# 04_Debugging.net
KiCad netlist of a schematic drawn in Altium Designer
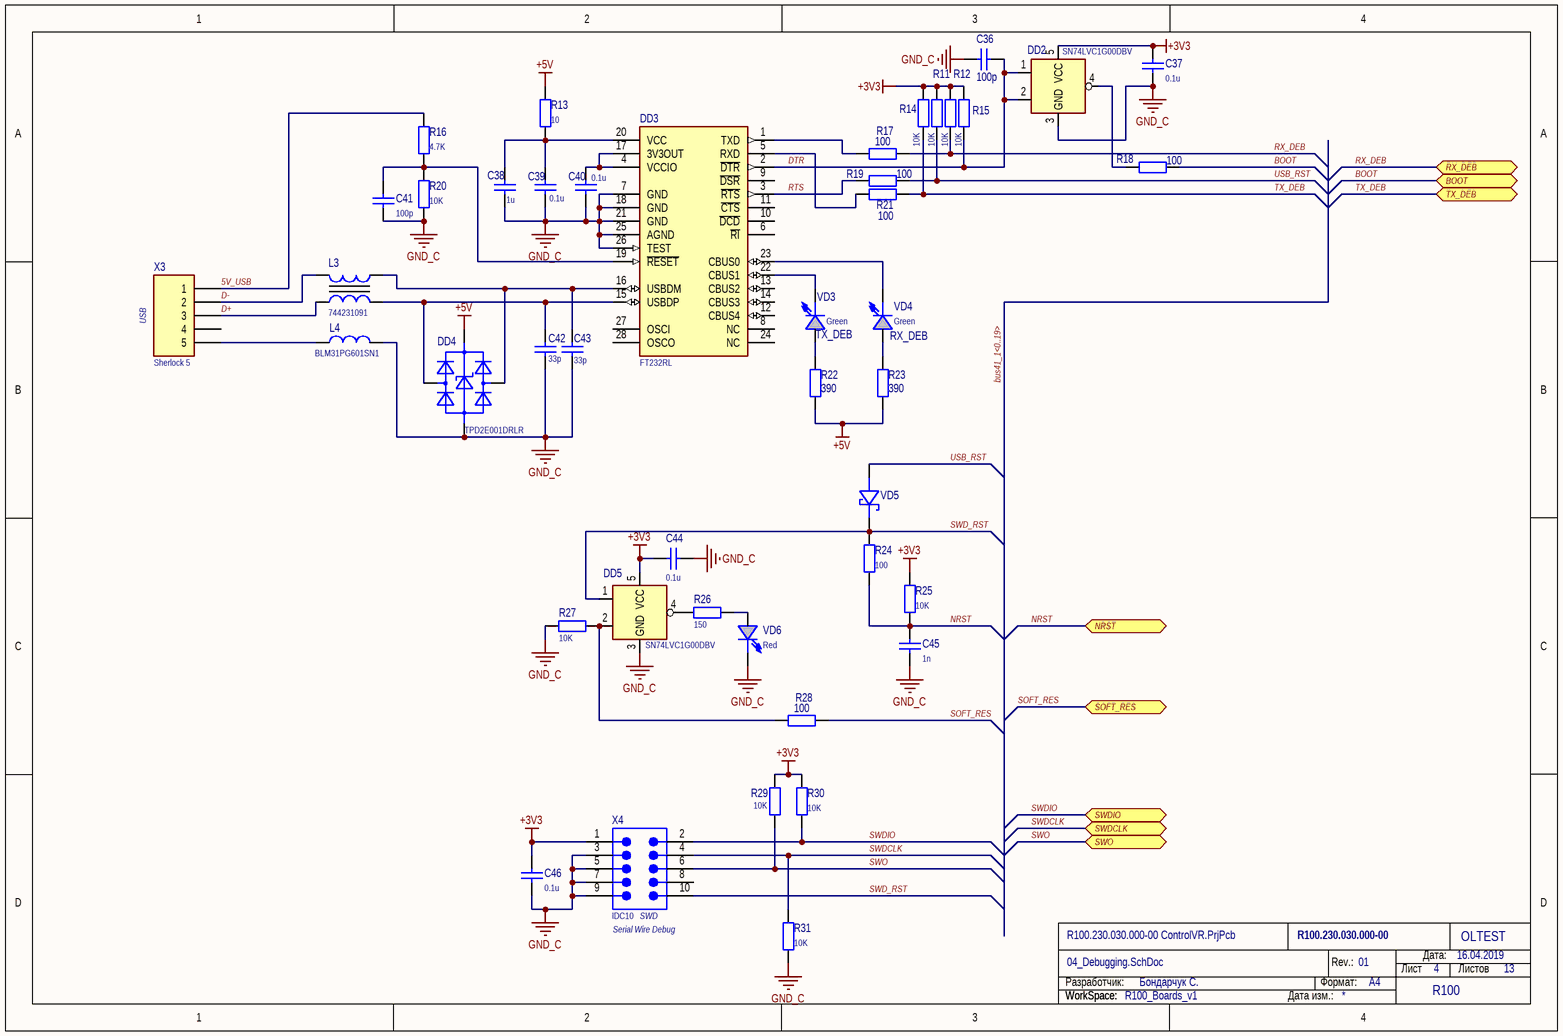
[diagram p0: 04_Debugging.SchDoc]

(export (version "E")
  (design (tool "Eeschema 10.0.6"))
  (components
    (comp (ref "C36")
      (value "100p")
      (footprint "mainLib:SMD_C_0603")
      (description "SMD C 0603 MURATA 100V 5% NP0")
      (fields (field (name "PARTNUMBER") "GRM1885C2A101JA01") (field (name "MANUFACTURER") "MURATA"))
      (libsource (lib "mainRCLib") (part "C0603 100p 100V 5%"))
    )
    (comp (ref "C37")
      (value "0.1u")
      (footprint "mainLib:SMD_C_0603")
      (description "SMD C 0603 MURATA 50V 10% X7R")
      (fields (field (name "PARTNUMBER") "GRM188R71H104K") (field (name "MANUFACTURER") "MURATA"))
      (libsource (lib "mainRCLib") (part "C0603 0.1u 50V 10%"))
    )
    (comp (ref "C38")
      (value "1u")
      (footprint "mainLib:SMD_C_0603")
      (description "SMD C 0603 MURATA 25V 10% X7R")
      (fields (field (name "PARTNUMBER") "GRM188R71E105KA12") (field (name "MANUFACTURER") "MURATA"))
      (libsource (lib "mainRCLib") (part "C0603 1uF 25V 10%"))
    )
    (comp (ref "C39")
      (value "0.1u")
      (footprint "mainLib:SMD_C_0603")
      (description "SMD C 0603 MURATA 50V 10% X7R")
      (fields (field (name "PARTNUMBER") "GRM188R71H104K") (field (name "MANUFACTURER") "MURATA"))
      (libsource (lib "mainRCLib") (part "C0603 0.1u 50V 10%"))
    )
    (comp (ref "C40")
      (value "0.1u")
      (footprint "mainLib:SMD_C_0603")
      (description "SMD C 0603 MURATA 50V 10% X7R")
      (fields (field (name "PARTNUMBER") "GRM188R71H104K") (field (name "MANUFACTURER") "MURATA"))
      (libsource (lib "mainRCLib") (part "C0603 0.1u 50V 10%"))
    )
    (comp (ref "C41")
      (value "100p")
      (footprint "mainLib:SMD_C_0603")
      (description "SMD C 0603 MURATA 100V 5% NP0")
      (fields (field (name "PARTNUMBER") "GRM1885C2A101JA01") (field (name "MANUFACTURER") "MURATA"))
      (libsource (lib "mainRCLib") (part "C0603 100p 100V 5%"))
    )
    (comp (ref "C42")
      (value "33p")
      (footprint "mainLib:SMD_C_0603")
      (description "SMD C 0603 MURATA 50V 5% NP0")
      (fields (field (name "PARTNUMBER") "GRM1885C1H330JA01") (field (name "MANUFACTURER") "MURATA"))
      (libsource (lib "mainRCLib") (part "C0603 33p 50V 5%"))
    )
    (comp (ref "C43")
      (value "33p")
      (footprint "mainLib:SMD_C_0603")
      (description "SMD C 0603 MURATA 50V 5% NP0")
      (fields (field (name "PARTNUMBER") "GRM1885C1H330JA01") (field (name "MANUFACTURER") "MURATA"))
      (libsource (lib "mainRCLib") (part "C0603 33p 50V 5%"))
    )
    (comp (ref "C44")
      (value "0.1u")
      (footprint "mainLib:SMD_C_0603")
      (description "SMD C 0603 MURATA 50V 10% X7R")
      (fields (field (name "PARTNUMBER") "GRM188R71H104K") (field (name "MANUFACTURER") "MURATA"))
      (libsource (lib "mainRCLib") (part "C0603 0.1u 50V 10%"))
    )
    (comp (ref "C45")
      (value "1n")
      (footprint "mainLib:SMD_C_0603")
      (description "SMD C 0603 MURATA 50V 5% NP0")
      (fields (field (name "PARTNUMBER") "GRM1885C1H102JA01") (field (name "MANUFACTURER") "MURATA"))
      (libsource (lib "mainRCLib") (part "C0603 1n 50V 5%"))
    )
    (comp (ref "C46")
      (value "0.1u")
      (footprint "mainLib:SMD_C_0603")
      (description "SMD C 0603 MURATA 50V 10% X7R")
      (fields (field (name "PARTNUMBER") "GRM188R71H104K") (field (name "MANUFACTURER") "MURATA"))
      (libsource (lib "mainRCLib") (part "C0603 0.1u 50V 10%"))
    )
    (comp (ref "DD2")
      (value "SN74LVC1G00DBV")
      (footprint "mainLib:SOT-23(DBV)")
      (description "2-in NAND")
      (fields (field (name "MANUFACTURER") "Texas Instruments"))
      (libsource (lib "mainLib") (part "SN74LVC1G00DBV"))
    )
    (comp (ref "DD3")
      (value "FT232RL")
      (footprint "mainLib:SSOP-28_M")
      (description "USB UART Asynchronous Serial Data Transfer Chip, 28-pin SSOP")
      (fields (field (name "MANUFACTURER") "FTDI"))
      (libsource (lib "mainLib") (part "FT232RL"))
    )
    (comp (ref "DD4")
      (value "TPD2E001DRLR")
      (footprint "mainLib:DRL5_M")
      (fields (field (name "MANUFACTURER") "Texas Instruments"))
      (libsource (lib "mainLib") (part "TPD2E001DRLR"))
    )
    (comp (ref "DD5")
      (value "SN74LVC1G00DBV")
      (footprint "mainLib:SOT-23(DBV)")
      (description "2-in NAND")
      (fields (field (name "MANUFACTURER") "Texas Instruments"))
      (libsource (lib "mainLib") (part "SN74LVC1G00DBV"))
    )
    (comp (ref "L3")
      (value "744231091")
      (footprint "mainLib:WE-CNSW-0805")
      (description "SMD Common Mode Noise Suppressor WE-CNSW, Z = 90 Ohm")
      (fields (field (name "MANUFACTURER") "Wurth Elektronik"))
      (libsource (lib "mainLib") (part "744231091"))
    )
    (comp (ref "L4")
      (value "BLM31PG601SN1")
      (footprint "mainLib:SMD_L_1206")
      (description "600R 1.5A (100MHz)")
      (fields (field (name "MANUFACTURER") "TDK") (field (name "PARTNUMBER") "BLM31PG601SN1"))
      (libsource (lib "mainLib") (part "BLM31PG601SN1"))
    )
    (comp (ref "R11")
      (value "10K")
      (footprint "SMD_R_0603")
      (description "SMD R 0603 VISHAY 0.1W 75V 1% 100ppm")
      (fields (field (name "PARTNUMBER") "CRCW060310K0FK") (field (name "MANUFACTURER") "VISHAY"))
      (libsource (lib "mainRCLib") (part "R0603 10К 1%"))
    )
    (comp (ref "R12")
      (value "10K")
      (footprint "SMD_R_0603")
      (description "SMD R 0603 VISHAY 0.1W 75V 1% 100ppm")
      (fields (field (name "PARTNUMBER") "CRCW060310K0FK") (field (name "MANUFACTURER") "VISHAY"))
      (libsource (lib "mainRCLib") (part "R0603 10К 1%"))
    )
    (comp (ref "R13")
      (value "10")
      (footprint "mainLib:SMD_R_0805")
      (description "SMD R 0805 VISHAY 0.125W 150V 1% 100ppm")
      (fields (field (name "PARTNUMBER") "CRCW080510R0FK") (field (name "MANUFACTURER") "VISHAY"))
      (libsource (lib "mainRCLib") (part "R0805 10 1%"))
    )
    (comp (ref "R14")
      (value "10K")
      (footprint "SMD_R_0603")
      (description "SMD R 0603 VISHAY 0.1W 75V 1% 100ppm")
      (fields (field (name "PARTNUMBER") "CRCW060310K0FK") (field (name "MANUFACTURER") "VISHAY"))
      (libsource (lib "mainRCLib") (part "R0603 10К 1%"))
    )
    (comp (ref "R15")
      (value "10K")
      (footprint "SMD_R_0603")
      (description "SMD R 0603 VISHAY 0.1W 75V 1% 100ppm")
      (fields (field (name "PARTNUMBER") "CRCW060310K0FK") (field (name "MANUFACTURER") "VISHAY"))
      (libsource (lib "mainRCLib") (part "R0603 10К 1%"))
    )
    (comp (ref "R16")
      (value "4.7K")
      (footprint "mainLib:SMD_R_0805")
      (description "SMD R 0805 VISHAY 0.125W 150V 1% 100ppm")
      (fields (field (name "PARTNUMBER") "CRCW08054K70FK") (field (name "MANUFACTURER") "VISHAY"))
      (libsource (lib "mainRCLib") (part "R0805 4.7K 1%"))
    )
    (comp (ref "R17")
      (value "100")
      (footprint "SMD_R_0603")
      (description "SMD R 0603 VISHAY 0.1W 75V 1% 100ppm")
      (fields (field (name "PARTNUMBER") "CRCW0603100RFK") (field (name "MANUFACTURER") "VISHAY"))
      (libsource (lib "") (part "R0603 100 1%_1"))
    )
    (comp (ref "R18")
      (value "100")
      (footprint "SMD_R_0603")
      (description "SMD R 0603 VISHAY 0.1W 75V 1% 100ppm")
      (fields (field (name "PARTNUMBER") "CRCW0603100RFK") (field (name "MANUFACTURER") "VISHAY"))
      (libsource (lib "") (part "R0603 100 1%_1"))
    )
    (comp (ref "R19")
      (value "100")
      (footprint "SMD_R_0603")
      (description "SMD R 0603 VISHAY 0.1W 75V 1% 100ppm")
      (fields (field (name "PARTNUMBER") "CRCW0603100RFK") (field (name "MANUFACTURER") "VISHAY"))
      (libsource (lib "") (part "R0603 100 1%_1"))
    )
    (comp (ref "R20")
      (value "10K")
      (footprint "mainLib:SMD_R_0805")
      (description "SMD R 0805 VISHAY 0.125W 150V 1% 100ppm")
      (fields (field (name "PARTNUMBER") "CRCW080510K0FK") (field (name "MANUFACTURER") "VISHAY"))
      (libsource (lib "mainRCLib") (part "R0805 10K 1%"))
    )
    (comp (ref "R21")
      (value "100")
      (footprint "SMD_R_0603")
      (description "SMD R 0603 VISHAY 0.1W 75V 1% 100ppm")
      (fields (field (name "PARTNUMBER") "CRCW0603100RFK") (field (name "MANUFACTURER") "VISHAY"))
      (libsource (lib "") (part "R0603 100 1%_1"))
    )
    (comp (ref "R22")
      (value "390")
      (footprint "mainLib:SMD_R_0805")
      (description "SMD R 0805 VISHAY 0.125W 150V 1% 100ppm")
      (fields (field (name "PARTNUMBER") "CRCW0805390RFK") (field (name "MANUFACTURER") "VISHAY"))
      (libsource (lib "mainRCLib") (part "R0805 390R 1%"))
    )
    (comp (ref "R23")
      (value "390")
      (footprint "mainLib:SMD_R_0805")
      (description "SMD R 0805 VISHAY 0.125W 150V 1% 100ppm")
      (fields (field (name "PARTNUMBER") "CRCW0805390RFK") (field (name "MANUFACTURER") "VISHAY"))
      (libsource (lib "mainRCLib") (part "R0805 390R 1%"))
    )
    (comp (ref "R24")
      (value "100")
      (footprint "SMD_R_0603")
      (description "SMD R 0603 VISHAY 0.1W 75V 1% 100ppm")
      (fields (field (name "PARTNUMBER") "CRCW0603100RFK") (field (name "MANUFACTURER") "VISHAY"))
      (libsource (lib "mainRCLib") (part "R0603 100 1%"))
    )
    (comp (ref "R25")
      (value "10K")
      (footprint "SMD_R_0603")
      (description "SMD R 0603 VISHAY 0.1W 75V 1% 100ppm")
      (fields (field (name "PARTNUMBER") "CRCW060310K0FK") (field (name "MANUFACTURER") "VISHAY"))
      (libsource (lib "mainRCLib") (part "R0603 10К 1%"))
    )
    (comp (ref "R26")
      (value "150")
      (footprint "mainLib:SMD_R_0805")
      (description "SMD 0805 VISHAY 0.125W 150V 1% 100ppm")
      (fields (field (name "PARTNUMBER") "CRCW0805150RFK") (field (name "MANUFACTURER") "VISHAY"))
      (libsource (lib "mainRCLib") (part "R0805 150 1%"))
    )
    (comp (ref "R27")
      (value "10K")
      (footprint "SMD_R_0603")
      (description "SMD R 0603 VISHAY 0.1W 75V 1% 100ppm")
      (fields (field (name "PARTNUMBER") "CRCW060310K0FK") (field (name "MANUFACTURER") "VISHAY"))
      (libsource (lib "") (part "R0603 10К 1%_1"))
    )
    (comp (ref "R28")
      (value "100")
      (footprint "SMD_R_0603")
      (description "SMD R 0603 VISHAY 0.1W 75V 1% 100ppm")
      (fields (field (name "PARTNUMBER") "CRCW0603100RFK") (field (name "MANUFACTURER") "VISHAY"))
      (libsource (lib "") (part "R0603 100 1%_1"))
    )
    (comp (ref "R29")
      (value "10K")
      (footprint "SMD_R_0603")
      (description "SMD R 0603 VISHAY 0.1W 75V 1% 100ppm")
      (fields (field (name "PARTNUMBER") "CRCW060310K0FK") (field (name "MANUFACTURER") "VISHAY"))
      (libsource (lib "mainRCLib") (part "R0603 10К 1%"))
    )
    (comp (ref "R30")
      (value "10K")
      (footprint "SMD_R_0603")
      (description "SMD R 0603 VISHAY 0.1W 75V 1% 100ppm")
      (fields (field (name "PARTNUMBER") "CRCW060310K0FK") (field (name "MANUFACTURER") "VISHAY"))
      (libsource (lib "mainRCLib") (part "R0603 10К 1%"))
    )
    (comp (ref "R31")
      (value "10K")
      (footprint "SMD_R_0603")
      (description "SMD R 0603 VISHAY 0.1W 75V 1% 100ppm")
      (fields (field (name "PARTNUMBER") "CRCW060310K0FK") (field (name "MANUFACTURER") "VISHAY"))
      (libsource (lib "mainRCLib") (part "R0603 10К 1%"))
    )
    (comp (ref "VD3")
      (value "Green")
      (footprint "mainLib:SMD_LED_LL_Green")
      (description "LED Green SMD")
      (fields (field (name "PARTNUMBER") "LL-S172GC-2A") (field (name "MANUFACTURER") "Lucky Light"))
      (libsource (lib "mainLib") (part "LL-S172GC-2A"))
    )
    (comp (ref "VD4")
      (value "Green")
      (footprint "mainLib:SMD_LED_LL_Green")
      (description "LED Green SMD")
      (fields (field (name "PARTNUMBER") "LL-S172GC-2A") (field (name "MANUFACTURER") "Lucky Light"))
      (libsource (lib "mainLib") (part "LL-S172GC-2A"))
    )
    (comp (ref "VD5")
      (value "MBR0540T1G")
      (footprint "mainLib:SOD-123")
      (description "0.5A/40V Schottky Diode (SOD-123)")
      (fields (field (name "MANUFACTURER") "ON Semiconductor"))
      (libsource (lib "mainLib") (part "MBR0540T1G"))
    )
    (comp (ref "VD6")
      (value "Red")
      (footprint "mainLib:SMD_LED_LL_Red")
      (description "LED Red SMD")
      (fields (field (name "PARTNUMBER") "LL-S172SC-2S") (field (name "MANUFACTURER") "Lucky Light"))
      (libsource (lib "mainLib") (part "LL-S172SC-2S"))
    )
    (comp (ref "X3")
      (value "Sherlock 5")
      (footprint "mainLib:35362-0550")
      (description "Sherlock 5 Top, 2A 125V 2mm")
      (fields (field (name "PARTNUMBER") "35362-0550") (field (name "MANUFACTURER") "MOLEX"))
      (libsource (lib "mainLib") (part "35362-0550"))
    )
    (comp (ref "X4")
      (value "IDC10")
      (footprint "mainLib:918510x324")
      (fields (field (name "PARTNUMBER") "09 18 510 6904") (field (name "PUBLISHER") "Altium Limited"))
      (libsource (lib "mainLib") (part "Harting IDC10 904"))
    )
  )
  (nets
    (net (code "2") (name "+3V3") (class "Default")
      (node (ref "C37") (pin "1") (pinfunction "1_1") (pintype "passive"))
      (node (ref "C44") (pin "2") (pinfunction "2_2") (pintype "passive"))
      (node (ref "C46") (pin "2") (pinfunction "2_2") (pintype "passive"))
      (node (ref "DD2") (pin "5") (pinfunction "VCC_5") (pintype "passive"))
      (node (ref "DD5") (pin "5") (pinfunction "VCC_5") (pintype "passive"))
      (node (ref "R11") (pin "2") (pinfunction "2_2") (pintype "passive"))
      (node (ref "R12") (pin "2") (pinfunction "2_2") (pintype "passive"))
      (node (ref "R14") (pin "2") (pinfunction "2_2") (pintype "passive"))
      (node (ref "R15") (pin "2") (pinfunction "2_2") (pintype "passive"))
      (node (ref "R25") (pin "2") (pinfunction "2_2") (pintype "passive"))
      (node (ref "R29") (pin "2") (pinfunction "2_2") (pintype "passive"))
      (node (ref "R30") (pin "2") (pinfunction "2_2") (pintype "passive"))
      (node (ref "X4") (pin "1") (pinfunction "1_1") (pintype "passive"))
    )
    (net (code "3") (name "+5V") (class "Default")
      (node (ref "DD4") (pin "1") (pinfunction "VCC_1") (pintype "power_in"))
      (node (ref "R13") (pin "2") (pinfunction "2_2") (pintype "passive"))
      (node (ref "R22") (pin "1") (pinfunction "1_1") (pintype "passive"))
      (node (ref "R23") (pin "1") (pinfunction "1_1") (pintype "passive"))
    )
    (net (code "4") (name "/5V_USB") (class "Default")
      (node (ref "R16") (pin "2") (pinfunction "2_2") (pintype "passive"))
      (node (ref "X3") (pin "1") (pinfunction "1_1") (pintype "passive"))
    )
    (net (code "5") (name "/BOOT") (class "Default")
      (node (ref "R18") (pin "2") (pinfunction "2_2") (pintype "passive"))
    )
    (net (code "6") (name "/D+") (class "Default")
      (node (ref "L3") (pin "1") (pinfunction "1_1") (pintype "passive"))
      (node (ref "X3") (pin "3") (pinfunction "3_3") (pintype "passive"))
    )
    (net (code "7") (name "/D-") (class "Default")
      (node (ref "L3") (pin "4") (pinfunction "4_4") (pintype "passive"))
      (node (ref "X3") (pin "2") (pinfunction "2_2") (pintype "passive"))
    )
    (net (code "8") (name "/DTR") (class "Default")
      (node (ref "C36") (pin "1") (pinfunction "1_1") (pintype "passive"))
      (node (ref "DD2") (pin "1") (pintype "passive"))
      (node (ref "DD2") (pin "2") (pintype "passive"))
      (node (ref "DD3") (pin "2") (pinfunction "~{DTR}_2") (pintype "output"))
      (node (ref "R15") (pin "1") (pinfunction "1_1") (pintype "passive"))
    )
    (net (code "9") (name "/NRST") (class "Default")
      (node (ref "C45") (pin "2") (pinfunction "2_2") (pintype "passive"))
      (node (ref "R24") (pin "1") (pinfunction "1_1") (pintype "passive"))
      (node (ref "R25") (pin "1") (pinfunction "1_1") (pintype "passive"))
    )
    (net (code "10") (name "/RTS") (class "Default")
      (node (ref "DD3") (pin "3") (pinfunction "~{RTS}_3") (pintype "output"))
      (node (ref "R19") (pin "1") (pinfunction "1_1") (pintype "passive"))
    )
    (net (code "11") (name "/RX_DEB") (class "Default")
      (node (ref "R12") (pin "1") (pinfunction "1_1") (pintype "passive"))
      (node (ref "R17") (pin "2") (pinfunction "2_2") (pintype "passive"))
    )
    (net (code "12") (name "/SOFT_RES") (class "Default")
      (node (ref "R28") (pin "2") (pinfunction "2_2") (pintype "passive"))
    )
    (net (code "13") (name "/SWDCLK") (class "Default")
      (node (ref "R31") (pin "2") (pinfunction "2_2") (pintype "passive"))
      (node (ref "X4") (pin "4") (pinfunction "4_4") (pintype "passive"))
    )
    (net (code "14") (name "/SWDIO") (class "Default")
      (node (ref "R30") (pin "1") (pinfunction "1_1") (pintype "passive"))
      (node (ref "X4") (pin "2") (pinfunction "2_2") (pintype "passive"))
    )
    (net (code "15") (name "/SWD_RST") (class "Default")
      (node (ref "DD5") (pin "1") (pintype "passive"))
      (node (ref "R24") (pin "2") (pinfunction "2_2") (pintype "passive"))
      (node (ref "VD5") (pin "1") (pinfunction "Cathode_1") (pintype "passive"))
      (node (ref "X4") (pin "10") (pinfunction "10_10") (pintype "passive"))
    )
    (net (code "16") (name "/SWO") (class "Default")
      (node (ref "R29") (pin "1") (pinfunction "1_1") (pintype "passive"))
      (node (ref "X4") (pin "6") (pinfunction "6_6") (pintype "passive"))
    )
    (net (code "17") (name "/TX_DEB") (class "Default")
      (node (ref "R14") (pin "1") (pinfunction "1_1") (pintype "passive"))
      (node (ref "R21") (pin "2") (pinfunction "2_2") (pintype "passive"))
    )
    (net (code "18") (name "/USB_RST") (class "Default")
      (node (ref "R11") (pin "1") (pinfunction "1_1") (pintype "passive"))
      (node (ref "R19") (pin "2") (pinfunction "2_2") (pintype "passive"))
      (node (ref "VD5") (pin "2") (pinfunction "Anode_2") (pintype "passive"))
    )
    (net (code "20") (name "GND_C") (class "Default")
      (node (ref "C36") (pin "2") (pinfunction "2_2") (pintype "passive"))
      (node (ref "C37") (pin "2") (pinfunction "2_2") (pintype "passive"))
      (node (ref "C38") (pin "1") (pinfunction "1_1") (pintype "passive"))
      (node (ref "C39") (pin "1") (pinfunction "1_1") (pintype "passive"))
      (node (ref "C40") (pin "1") (pinfunction "1_1") (pintype "passive"))
      (node (ref "C41") (pin "1") (pinfunction "1_1") (pintype "passive"))
      (node (ref "C42") (pin "2") (pinfunction "2_2") (pintype "passive"))
      (node (ref "C43") (pin "2") (pinfunction "2_2") (pintype "passive"))
      (node (ref "C44") (pin "1") (pinfunction "1_1") (pintype "passive"))
      (node (ref "C45") (pin "1") (pinfunction "1_1") (pintype "passive"))
      (node (ref "C46") (pin "1") (pinfunction "1_1") (pintype "passive"))
      (node (ref "DD2") (pin "3") (pinfunction "GND_3") (pintype "passive"))
      (node (ref "DD3") (pin "18") (pinfunction "GND_18") (pintype "power_in"))
      (node (ref "DD3") (pin "21") (pinfunction "GND_21") (pintype "power_in"))
      (node (ref "DD3") (pin "25") (pinfunction "AGND_25") (pintype "power_in"))
      (node (ref "DD3") (pin "26") (pinfunction "TEST_26") (pintype "input"))
      (node (ref "DD3") (pin "7") (pinfunction "GND_7") (pintype "power_in"))
      (node (ref "DD4") (pin "4") (pinfunction "GND_4") (pintype "power_in"))
      (node (ref "DD5") (pin "3") (pinfunction "GND_3") (pintype "passive"))
      (node (ref "L4") (pin "2") (pinfunction "2_2") (pintype "passive"))
      (node (ref "R20") (pin "1") (pinfunction "1_1") (pintype "passive"))
      (node (ref "R27") (pin "2") (pinfunction "2_2") (pintype "passive"))
      (node (ref "R31") (pin "1") (pinfunction "1_1") (pintype "passive"))
      (node (ref "VD6") (pin "2") (pinfunction "CATHODE_2") (pintype "passive"))
      (node (ref "X4") (pin "3") (pinfunction "3_3") (pintype "passive"))
      (node (ref "X4") (pin "5") (pinfunction "5_5") (pintype "passive"))
      (node (ref "X4") (pin "7") (pinfunction "7_7") (pintype "passive"))
      (node (ref "X4") (pin "9") (pinfunction "9_9") (pintype "passive"))
    )
    (net (code "21") (name "Net-(DD2-Pad4)") (class "Default")
      (node (ref "DD2") (pin "4") (pintype "passive"))
      (node (ref "R18") (pin "1") (pinfunction "1_1") (pintype "passive"))
    )
    (net (code "22") (name "Net-(DD3-3V3OUT)") (class "Default")
      (node (ref "C40") (pin "2") (pinfunction "2_2") (pintype "passive"))
      (node (ref "DD3") (pin "17") (pinfunction "3V3OUT_17") (pintype "passive"))
      (node (ref "DD3") (pin "4") (pinfunction "VCCIO_4") (pintype "power_in"))
    )
    (net (code "23") (name "Net-(DD3-CBUS0)") (class "Default")
      (node (ref "DD3") (pin "23") (pinfunction "CBUS0_23") (pintype "bidirectional"))
      (node (ref "VD4") (pin "2") (pinfunction "CATHODE_2") (pintype "passive"))
    )
    (net (code "24") (name "Net-(DD3-CBUS1)") (class "Default")
      (node (ref "DD3") (pin "22") (pinfunction "CBUS1_22") (pintype "bidirectional"))
      (node (ref "VD3") (pin "2") (pinfunction "CATHODE_2") (pintype "passive"))
    )
    (net (code "25") (name "Net-(DD3-RXD)") (class "Default")
      (node (ref "DD3") (pin "5") (pinfunction "RXD_5") (pintype "passive"))
      (node (ref "R21") (pin "1") (pinfunction "1_1") (pintype "passive"))
    )
    (net (code "26") (name "Net-(DD3-TXD)") (class "Default")
      (node (ref "DD3") (pin "1") (pinfunction "TXD_1") (pintype "output"))
      (node (ref "R17") (pin "1") (pinfunction "1_1") (pintype "passive"))
    )
    (net (code "27") (name "Net-(DD3-USBDM)") (class "Default")
      (node (ref "C43") (pin "1") (pinfunction "1_1") (pintype "passive"))
      (node (ref "DD3") (pin "16") (pinfunction "USBDM_16") (pintype "bidirectional"))
      (node (ref "DD4") (pin "5") (pinfunction "IO2_5") (pintype "passive"))
      (node (ref "L3") (pin "3") (pinfunction "3_3") (pintype "passive"))
    )
    (net (code "28") (name "Net-(DD3-USBDP)") (class "Default")
      (node (ref "C42") (pin "1") (pinfunction "1_1") (pintype "passive"))
      (node (ref "DD3") (pin "15") (pinfunction "USBDP_15") (pintype "bidirectional"))
      (node (ref "DD4") (pin "3") (pinfunction "IO1_3") (pintype "passive"))
      (node (ref "L3") (pin "2") (pinfunction "2_2") (pintype "passive"))
    )
    (net (code "29") (name "Net-(DD3-VCC)") (class "Default")
      (node (ref "C38") (pin "2") (pinfunction "2_2") (pintype "passive"))
      (node (ref "C39") (pin "2") (pinfunction "2_2") (pintype "passive"))
      (node (ref "DD3") (pin "20") (pinfunction "VCC_20") (pintype "power_in"))
      (node (ref "R13") (pin "1") (pinfunction "1_1") (pintype "passive"))
    )
    (net (code "30") (name "Net-(DD3-~{RESET})") (class "Default")
      (node (ref "C41") (pin "2") (pinfunction "2_2") (pintype "passive"))
      (node (ref "DD3") (pin "19") (pinfunction "~{RESET}_19") (pintype "input"))
      (node (ref "R16") (pin "1") (pinfunction "1_1") (pintype "passive"))
      (node (ref "R20") (pin "2") (pinfunction "2_2") (pintype "passive"))
    )
    (net (code "31") (name "Net-(DD5-Pad2)") (class "Default")
      (node (ref "DD5") (pin "2") (pintype "passive"))
      (node (ref "R27") (pin "1") (pinfunction "1_1") (pintype "passive"))
      (node (ref "R28") (pin "1") (pinfunction "1_1") (pintype "passive"))
    )
    (net (code "32") (name "Net-(DD5-Pad4)") (class "Default")
      (node (ref "DD5") (pin "4") (pintype "passive"))
      (node (ref "R26") (pin "1") (pinfunction "1_1") (pintype "passive"))
    )
    (net (code "33") (name "Net-(L4-Pad1)") (class "Default")
      (node (ref "L4") (pin "1") (pinfunction "1_1") (pintype "passive"))
      (node (ref "X3") (pin "5") (pinfunction "5_5") (pintype "passive"))
    )
    (net (code "34") (name "Net-(VD3-ANODE)") (class "Default")
      (node (ref "R22") (pin "2") (pinfunction "2_2") (pintype "passive"))
      (node (ref "VD3") (pin "1") (pinfunction "ANODE_1") (pintype "passive"))
    )
    (net (code "35") (name "Net-(VD4-ANODE)") (class "Default")
      (node (ref "R23") (pin "2") (pinfunction "2_2") (pintype "passive"))
      (node (ref "VD4") (pin "1") (pinfunction "ANODE_1") (pintype "passive"))
    )
    (net (code "36") (name "Net-(VD6-ANODE)") (class "Default")
      (node (ref "R26") (pin "2") (pinfunction "2_2") (pintype "passive"))
      (node (ref "VD6") (pin "1") (pinfunction "ANODE_1") (pintype "passive"))
    )
    (net (code "37") (name "unconnected-(DD3-CBUS2-Pad13)") (class "Default")
      (node (ref "DD3") (pin "13") (pinfunction "CBUS2_13") (pintype "bidirectional"))
    )
    (net (code "38") (name "unconnected-(DD3-CBUS3-Pad14)") (class "Default")
      (node (ref "DD3") (pin "14") (pinfunction "CBUS3_14") (pintype "bidirectional"))
    )
    (net (code "39") (name "unconnected-(DD3-CBUS4-Pad12)") (class "Default")
      (node (ref "DD3") (pin "12") (pinfunction "CBUS4_12") (pintype "bidirectional"))
    )
    (net (code "40") (name "unconnected-(DD3-NC-Pad8)") (class "Default")
      (node (ref "DD3") (pin "8") (pinfunction "NC_8") (pintype "passive"))
    )
    (net (code "41") (name "unconnected-(DD3-NC-Pad24)") (class "Default")
      (node (ref "DD3") (pin "24") (pinfunction "NC_24") (pintype "passive"))
    )
    (net (code "42") (name "unconnected-(DD3-OSCI-Pad27)") (class "Default")
      (node (ref "DD3") (pin "27") (pinfunction "OSCI_27") (pintype "passive"))
    )
    (net (code "43") (name "unconnected-(DD3-OSCO-Pad28)") (class "Default")
      (node (ref "DD3") (pin "28") (pinfunction "OSCO_28") (pintype "passive"))
    )
    (net (code "44") (name "unconnected-(DD3-~{CTS}-Pad11)") (class "Default")
      (node (ref "DD3") (pin "11") (pinfunction "~{CTS}_11") (pintype "passive"))
    )
    (net (code "45") (name "unconnected-(DD3-~{DCD}-Pad10)") (class "Default")
      (node (ref "DD3") (pin "10") (pinfunction "~{DCD}_10") (pintype "passive"))
    )
    (net (code "46") (name "unconnected-(DD3-~{DSR}-Pad9)") (class "Default")
      (node (ref "DD3") (pin "9") (pinfunction "~{DSR}_9") (pintype "passive"))
    )
    (net (code "47") (name "unconnected-(DD3-~{RI}-Pad6)") (class "Default")
      (node (ref "DD3") (pin "6") (pinfunction "~{RI}_6") (pintype "passive"))
    )
    (net (code "48") (name "unconnected-(X3-Pad4)") (class "Default")
      (node (ref "X3") (pin "4") (pinfunction "4_4") (pintype "passive"))
    )
    (net (code "49") (name "unconnected-(X4-Pad8)") (class "Default")
      (node (ref "X4") (pin "8") (pinfunction "8_8") (pintype "passive"))
    )
  )
)
